# AmbaSat-03-BME680.net
KiCad netlist of a schematic drawn in EAGLE
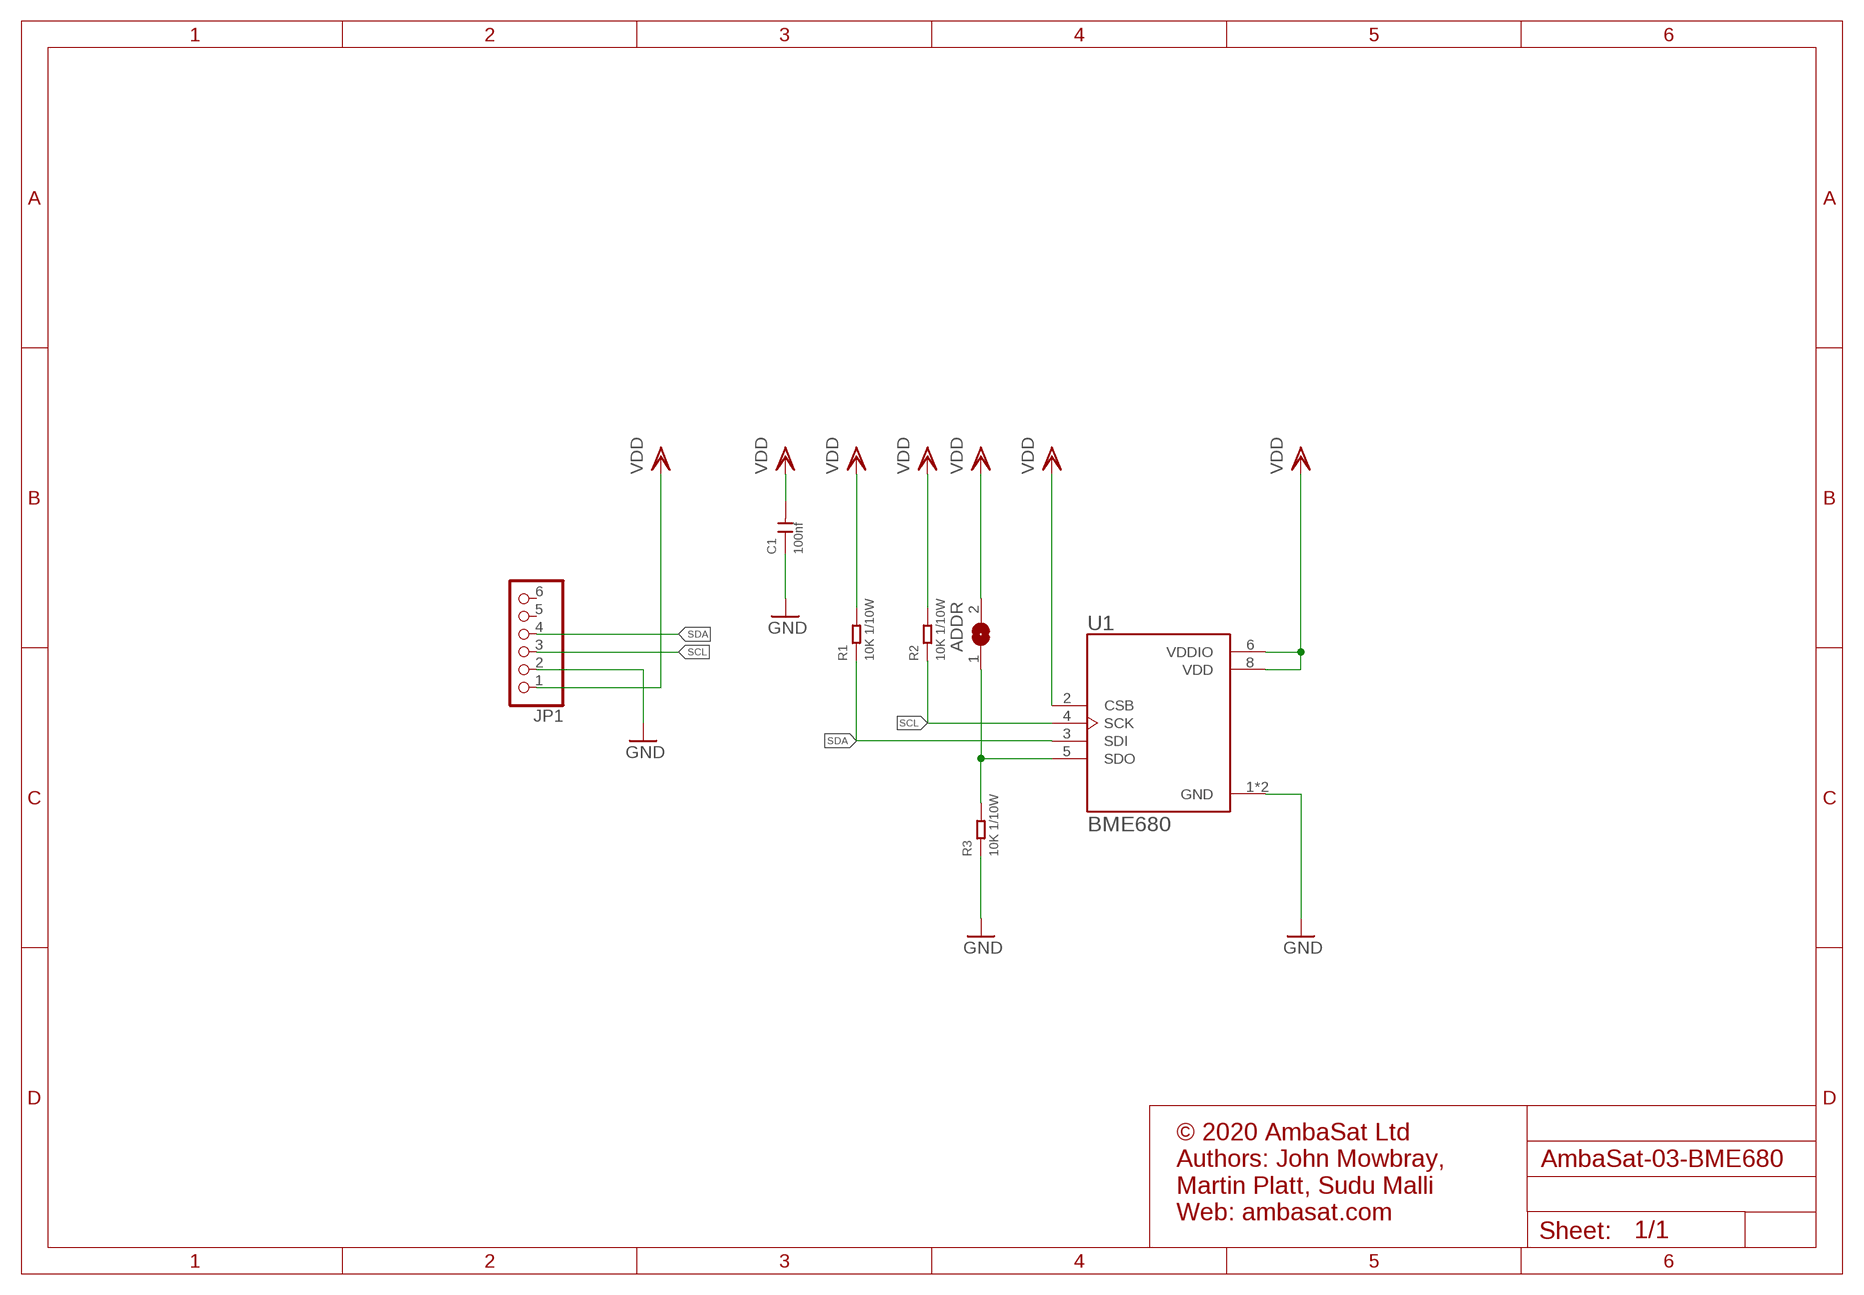
[diagram p0: schematic, sheet 1]

(export (version "E")
  (design (tool "Eeschema 10.0.6"))
  (components
    (comp (ref "ADDR")
      (value "SJ")
      (footprint "eagle-import:SJ")
      (libsource (lib "eagle-import") (part "SJ"))
    )
    (comp (ref "C1")
      (value "100nf")
      (footprint "eagle-import:C0603")
      (fields (field (name "MPN") "CC0603KRX7R9BB104"))
      (libsource (lib "eagle-import") (part "CERAMIC-100NF-50V-10%-X7R(0603)"))
    )
    (comp (ref "JP1")
      (value "HEADER-1X6")
      (footprint "eagle-import:1X06_OVAL")
      (libsource (lib "eagle-import") (part "HEADER-1X6"))
    )
    (comp (ref "R1")
      (value "10K 1/10W")
      (footprint "eagle-import:R0603")
      (fields (field (name "MPN") "RC0603JR-0710KL"))
      (libsource (lib "eagle-import") (part "SMD-RES-10K-5%-1/10W(0603)"))
    )
    (comp (ref "R2")
      (value "10K 1/10W")
      (footprint "eagle-import:R0603")
      (fields (field (name "MPN") "RC0603JR-0710KL"))
      (libsource (lib "eagle-import") (part "SMD-RES-10K-5%-1/10W(0603)"))
    )
    (comp (ref "R3")
      (value "10K 1/10W")
      (footprint "eagle-import:R0603")
      (fields (field (name "MPN") "RC0603JR-0710KL"))
      (libsource (lib "eagle-import") (part "SMD-RES-10K-5%-1/10W(0603)"))
    )
    (comp (ref "U1")
      (value "BME680")
      (footprint "eagle-import:PSON80P300X300X100-8N")
      (fields (field (name "MF") "Bosch Sensortec"))
      (libsource (lib "eagle-import") (part "BME680"))
    )
  )
  (nets
    (net (code "1") (name "GND") (class "Default")
      (node (ref "C1") (pin "1") (pinfunction "1_1") (pintype "passive"))
      (node (ref "JP1") (pin "2") (pinfunction "2_2") (pintype "passive"))
      (node (ref "R3") (pin "1") (pinfunction "1_1") (pintype "passive"))
      (node (ref "U1") (pin "1") (pinfunction "GND_1") (pintype "power_in"))
      (node (ref "U1") (pin "7") (pinfunction "GND_7") (pintype "power_in"))
    )
    (net (code "2") (name "Net-(U1-SDO)") (class "Default")
      (node (ref "ADDR") (pin "1") (pinfunction "1_1") (pintype "passive"))
      (node (ref "R3") (pin "2") (pinfunction "2_2") (pintype "passive"))
      (node (ref "U1") (pin "5") (pinfunction "SDO_5") (pintype "bidirectional"))
    )
    (net (code "3") (name "SCL") (class "Default")
      (node (ref "JP1") (pin "3") (pinfunction "3_3") (pintype "passive"))
      (node (ref "R2") (pin "1") (pinfunction "1_1") (pintype "passive"))
      (node (ref "U1") (pin "4") (pinfunction "SCK_4") (pintype "input"))
    )
    (net (code "4") (name "SDA") (class "Default")
      (node (ref "JP1") (pin "4") (pinfunction "4_4") (pintype "passive"))
      (node (ref "R1") (pin "1") (pinfunction "1_1") (pintype "passive"))
      (node (ref "U1") (pin "3") (pinfunction "SDI_3") (pintype "bidirectional"))
    )
    (net (code "5") (name "VDD") (class "Default")
      (node (ref "ADDR") (pin "2") (pinfunction "2_2") (pintype "passive"))
      (node (ref "C1") (pin "2") (pinfunction "2_2") (pintype "passive"))
      (node (ref "JP1") (pin "1") (pinfunction "1_1") (pintype "passive"))
      (node (ref "R1") (pin "2") (pinfunction "2_2") (pintype "passive"))
      (node (ref "R2") (pin "2") (pinfunction "2_2") (pintype "passive"))
      (node (ref "U1") (pin "2") (pinfunction "CSB_2") (pintype "input"))
      (node (ref "U1") (pin "6") (pinfunction "VDDIO_6") (pintype "power_in"))
      (node (ref "U1") (pin "8") (pinfunction "VDD_8") (pintype "power_in"))
    )
    (net (code "6") (name "unconnected-(JP1-Pad5)") (class "Default")
      (node (ref "JP1") (pin "5") (pinfunction "5_5") (pintype "passive"))
    )
    (net (code "7") (name "unconnected-(JP1-Pad6)") (class "Default")
      (node (ref "JP1") (pin "6") (pinfunction "6_6") (pintype "passive"))
    )
  )
)
